# Main.net
KiCad netlist of a schematic drawn in Altium Designer
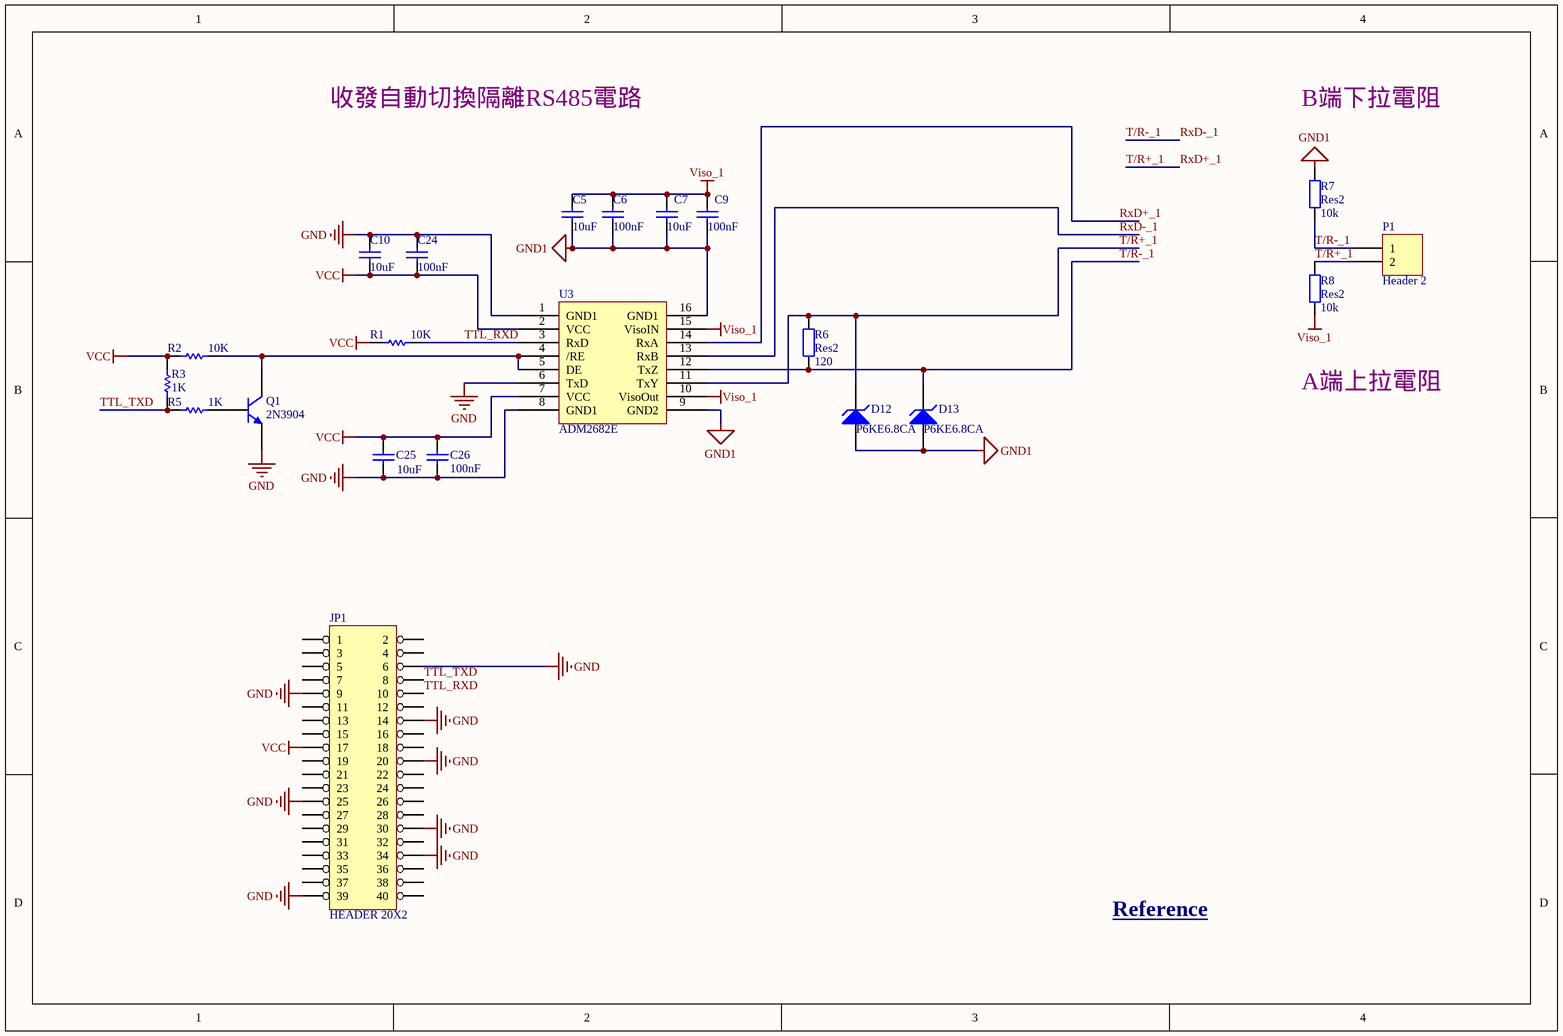
[diagram p0: Main.SchDoc]

(export (version "E")
  (design (tool "Eeschema 10.0.6"))
  (components
    (comp (ref "C5")
      (value "10uF")
      (footprint "0805_C")
      (description "Cap-10uF")
      (fields (field (name "Comment") "Cap Semi") (field (name "PUBLISHER") "Altium Limited"))
      (libsource (lib "Miscellaneous Devices") (part "Cap Semi"))
    )
    (comp (ref "C6")
      (value "100nF")
      (footprint "SMD-0402C")
      (description "Cap-0.1uF")
      (fields (field (name "Comment") "Cap Semi") (field (name "PUBLISHER") "Altium Limited"))
      (libsource (lib "Miscellaneous Devices") (part "Cap Semi"))
    )
    (comp (ref "C7")
      (value "10uF")
      (footprint "0805_C")
      (description "Cap-10uF")
      (fields (field (name "Comment") "Cap Semi") (field (name "PUBLISHER") "Altium Limited"))
      (libsource (lib "Miscellaneous Devices") (part "Cap Semi"))
    )
    (comp (ref "C9")
      (value "100nF")
      (footprint "SMD-0402C")
      (description "Cap-0.1uF")
      (fields (field (name "Comment") "Cap Semi") (field (name "PUBLISHER") "Altium Limited"))
      (libsource (lib "Miscellaneous Devices") (part "Cap Semi"))
    )
    (comp (ref "C10")
      (value "10uF")
      (footprint "0805_C")
      (description "Cap-10uF")
      (fields (field (name "Comment") "Cap Semi") (field (name "PUBLISHER") "Altium Limited"))
      (libsource (lib "Miscellaneous Devices") (part "Cap Semi"))
    )
    (comp (ref "C24")
      (value "100nF")
      (footprint "SMD-0402C")
      (description "Cap-0.1uF")
      (fields (field (name "Comment") "Cap Semi") (field (name "PUBLISHER") "Altium Limited"))
      (libsource (lib "Miscellaneous Devices") (part "Cap Semi"))
    )
    (comp (ref "C25")
      (value "10uF")
      (footprint "0805_C")
      (description "Cap-10uF")
      (fields (field (name "Comment") "Cap Semi") (field (name "PUBLISHER") "Altium Limited"))
      (libsource (lib "Miscellaneous Devices") (part "Cap Semi"))
    )
    (comp (ref "C26")
      (value "100nF")
      (footprint "SMD-0402C")
      (description "Cap-0.1uF")
      (fields (field (name "Comment") "Cap Semi") (field (name "PUBLISHER") "Altium Limited"))
      (libsource (lib "Miscellaneous Devices") (part "Cap Semi"))
    )
    (comp (ref "D12")
      (value "P6KE6.8CA")
      (footprint "DIODE-0.4")
      (description "Zener Diode")
      (fields (field (name "PUBLISHER") "Altium Limited"))
      (libsource (lib "i-SchLib") (part "D Zener"))
    )
    (comp (ref "D13")
      (value "P6KE6.8CA")
      (footprint "DIODE-0.4")
      (description "Zener Diode")
      (fields (field (name "PUBLISHER") "Altium Limited"))
      (libsource (lib "i-SchLib") (part "D Zener"))
    )
    (comp (ref "JP1")
      (value "HEADER 20X2")
      (footprint "HDR2X20")
      (libsource (lib "YB070WVHB01-50O-E1-SCH") (part "HEADER 20X2"))
    )
    (comp (ref "P1")
      (value "Header 2")
      (footprint "歐式端子*2p")
      (description "Header, 2-Pin")
      (fields (field (name "PUBLISHER") "Altium Limited"))
      (libsource (lib "Miscellaneous Connectors") (part "Header 2"))
    )
    (comp (ref "Q1")
      (value "2N3904")
      (footprint "SOT23_N")
      (description "NPN General Purpose Amplifier")
      (fields (field (name "PUBLISHER") "Altium Limited"))
      (libsource (lib "Miscellaneous Devices") (part "2N3904"))
    )
    (comp (ref "R1")
      (value "10K")
      (footprint "SMD-0402-RES")
      (description "Res-10k")
      (fields (field (name "Comment") "Res Semi") (field (name "PUBLISHER") "Altium Limited"))
      (libsource (lib "Miscellaneous Devices") (part "Res Semi"))
    )
    (comp (ref "R2")
      (value "10K")
      (footprint "SMD-0402-RES")
      (description "Res-10k")
      (fields (field (name "Comment") "Res Semi") (field (name "PUBLISHER") "Altium Limited"))
      (libsource (lib "Miscellaneous Devices") (part "Res Semi"))
    )
    (comp (ref "R3")
      (value "1K")
      (footprint "SMD-0402-RES")
      (description "Res-1k")
      (fields (field (name "Comment") "Res Semi") (field (name "PUBLISHER") "Altium Limited"))
      (libsource (lib "Miscellaneous Devices") (part "Res Semi"))
    )
    (comp (ref "R5")
      (value "1K")
      (footprint "SMD-0402-RES")
      (description "Res-1k")
      (fields (field (name "Comment") "Res Semi") (field (name "PUBLISHER") "Altium Limited"))
      (libsource (lib "Miscellaneous Devices") (part "Res Semi"))
    )
    (comp (ref "R6")
      (value "Res2")
      (footprint "SMD-0402-RES")
      (description "Res-120")
      (fields (field (name "ALTIUM_VALUE") "120") (field (name "PUBLISHER") "Altium Limited"))
      (libsource (lib "Miscellaneous Devices") (part "Res2"))
    )
    (comp (ref "R7")
      (value "Res2")
      (footprint "SMD-0402-RES")
      (description "Res-10k")
      (fields (field (name "ALTIUM_VALUE") "10k") (field (name "PUBLISHER") "Altium Limited"))
      (libsource (lib "Miscellaneous Devices") (part "Res2"))
    )
    (comp (ref "R8")
      (value "Res2")
      (footprint "SMD-0402-RES")
      (description "Res-10k")
      (fields (field (name "ALTIUM_VALUE") "10k") (field (name "PUBLISHER") "Altium Limited"))
      (libsource (lib "Miscellaneous Devices") (part "Res2"))
    )
    (comp (ref "U3")
      (value "ADM2682E")
      (footprint "SOIC127P1030-16N")
      (description "isolation RS422 with isolated power")
      (libsource (lib "i-SchLib") (part "ADM2682E"))
    )
  )
  (nets
    (net (code "1") (name "/RxD+_1") (class "Default")
      (node (ref "D12") (pin "2") (pinfunction "K_2") (pintype "passive"))
      (node (ref "P1") (pin "2") (pinfunction "2_2") (pintype "passive"))
      (node (ref "R6") (pin "2") (pinfunction "2_2") (pintype "passive"))
      (node (ref "R8") (pin "2") (pinfunction "2_2") (pintype "passive"))
      (node (ref "U3") (pin "11") (pinfunction "TxY_11") (pintype "passive"))
      (node (ref "U3") (pin "14") (pinfunction "RxA_14") (pintype "passive"))
    )
    (net (code "2") (name "/RxD-_1") (class "Default")
      (node (ref "D13") (pin "2") (pinfunction "K_2") (pintype "passive"))
      (node (ref "P1") (pin "1") (pinfunction "1_1") (pintype "passive"))
      (node (ref "R6") (pin "1") (pinfunction "1_1") (pintype "passive"))
      (node (ref "R7") (pin "1") (pinfunction "1_1") (pintype "passive"))
      (node (ref "U3") (pin "12") (pinfunction "TxZ_12") (pintype "passive"))
      (node (ref "U3") (pin "13") (pinfunction "RxB_13") (pintype "passive"))
    )
    (net (code "3") (name "/TTL_RXD") (class "Default")
      (node (ref "JP1") (pin "10") (pinfunction "10_10") (pintype "passive"))
      (node (ref "R1") (pin "1") (pinfunction "1_1") (pintype "passive"))
      (node (ref "U3") (pin "3") (pinfunction "RxD_3") (pintype "passive"))
    )
    (net (code "4") (name "/TTL_TXD") (class "Default")
      (node (ref "JP1") (pin "8") (pinfunction "8_8") (pintype "passive"))
      (node (ref "R3") (pin "2") (pinfunction "2_2") (pintype "passive"))
      (node (ref "R5") (pin "2") (pinfunction "2_2") (pintype "passive"))
    )
    (net (code "5") (name "GND") (class "Default")
      (node (ref "C10") (pin "2") (pinfunction "2_2") (pintype "passive"))
      (node (ref "C24") (pin "2") (pinfunction "2_2") (pintype "passive"))
      (node (ref "C25") (pin "1") (pinfunction "1_1") (pintype "passive"))
      (node (ref "C26") (pin "2") (pinfunction "2_2") (pintype "passive"))
      (node (ref "JP1") (pin "14") (pinfunction "14_14") (pintype "passive"))
      (node (ref "JP1") (pin "20") (pinfunction "20_20") (pintype "passive"))
      (node (ref "JP1") (pin "25") (pinfunction "25_25") (pintype "passive"))
      (node (ref "JP1") (pin "30") (pinfunction "30_30") (pintype "passive"))
      (node (ref "JP1") (pin "34") (pinfunction "34_34") (pintype "passive"))
      (node (ref "JP1") (pin "39") (pinfunction "39_39") (pintype "passive"))
      (node (ref "JP1") (pin "6") (pinfunction "6_6") (pintype "passive"))
      (node (ref "JP1") (pin "9") (pinfunction "9_9") (pintype "passive"))
      (node (ref "Q1") (pin "2") (pinfunction "E_2") (pintype "passive"))
      (node (ref "U3") (pin "1") (pinfunction "GND1_1") (pintype "passive"))
      (node (ref "U3") (pin "6") (pinfunction "TxD_6") (pintype "passive"))
      (node (ref "U3") (pin "8") (pinfunction "GND1_8") (pintype "passive"))
    )
    (net (code "6") (name "GND1") (class "Default")
      (node (ref "C5") (pin "1") (pinfunction "1_1") (pintype "passive"))
      (node (ref "C6") (pin "1") (pinfunction "1_1") (pintype "passive"))
      (node (ref "C7") (pin "1") (pinfunction "1_1") (pintype "passive"))
      (node (ref "C9") (pin "1") (pinfunction "1_1") (pintype "passive"))
      (node (ref "D12") (pin "1") (pinfunction "A_1") (pintype "passive"))
      (node (ref "D13") (pin "1") (pinfunction "A_1") (pintype "passive"))
      (node (ref "R7") (pin "2") (pinfunction "2_2") (pintype "passive"))
      (node (ref "U3") (pin "16") (pinfunction "GND1_16") (pintype "passive"))
      (node (ref "U3") (pin "9") (pinfunction "GND2_9") (pintype "passive"))
    )
    (net (code "7") (name "Net-(Q1-B)") (class "Default")
      (node (ref "Q1") (pin "3") (pinfunction "B_3") (pintype "passive"))
      (node (ref "R5") (pin "1") (pinfunction "1_1") (pintype "passive"))
    )
    (net (code "8") (name "Net-(Q1-C)") (class "Default")
      (node (ref "Q1") (pin "1") (pinfunction "C_1") (pintype "passive"))
      (node (ref "R2") (pin "1") (pinfunction "1_1") (pintype "passive"))
      (node (ref "U3") (pin "4") (pinfunction "/RE_4") (pintype "passive"))
      (node (ref "U3") (pin "5") (pinfunction "DE_5") (pintype "passive"))
    )
    (net (code "9") (name "VCC") (class "Default")
      (node (ref "C10") (pin "1") (pinfunction "1_1") (pintype "passive"))
      (node (ref "C24") (pin "1") (pinfunction "1_1") (pintype "passive"))
      (node (ref "C25") (pin "2") (pinfunction "2_2") (pintype "passive"))
      (node (ref "C26") (pin "1") (pinfunction "1_1") (pintype "passive"))
      (node (ref "JP1") (pin "17") (pinfunction "17_17") (pintype "passive"))
      (node (ref "R1") (pin "2") (pinfunction "2_2") (pintype "passive"))
      (node (ref "R2") (pin "2") (pinfunction "2_2") (pintype "passive"))
      (node (ref "R3") (pin "1") (pinfunction "1_1") (pintype "passive"))
      (node (ref "U3") (pin "2") (pinfunction "VCC_2") (pintype "passive"))
      (node (ref "U3") (pin "7") (pinfunction "VCC_7") (pintype "passive"))
    )
    (net (code "10") (name "Viso_1") (class "Default")
      (node (ref "C5") (pin "2") (pinfunction "2_2") (pintype "passive"))
      (node (ref "C6") (pin "2") (pinfunction "2_2") (pintype "passive"))
      (node (ref "C7") (pin "2") (pinfunction "2_2") (pintype "passive"))
      (node (ref "C9") (pin "2") (pinfunction "2_2") (pintype "passive"))
      (node (ref "R8") (pin "1") (pinfunction "1_1") (pintype "passive"))
      (node (ref "U3") (pin "10") (pinfunction "VisoOut_10") (pintype "passive"))
      (node (ref "U3") (pin "15") (pinfunction "VisoIN_15") (pintype "passive"))
    )
    (net (code "11") (name "unconnected-(JP1-Pad1)") (class "Default")
      (node (ref "JP1") (pin "1") (pinfunction "1_1") (pintype "passive"))
    )
    (net (code "12") (name "unconnected-(JP1-Pad2)") (class "Default")
      (node (ref "JP1") (pin "2") (pinfunction "2_2") (pintype "passive"))
    )
    (net (code "13") (name "unconnected-(JP1-Pad3)") (class "Default")
      (node (ref "JP1") (pin "3") (pinfunction "3_3") (pintype "passive"))
    )
    (net (code "14") (name "unconnected-(JP1-Pad4)") (class "Default")
      (node (ref "JP1") (pin "4") (pinfunction "4_4") (pintype "passive"))
    )
    (net (code "15") (name "unconnected-(JP1-Pad5)") (class "Default")
      (node (ref "JP1") (pin "5") (pinfunction "5_5") (pintype "passive"))
    )
    (net (code "16") (name "unconnected-(JP1-Pad7)") (class "Default")
      (node (ref "JP1") (pin "7") (pinfunction "7_7") (pintype "passive"))
    )
    (net (code "17") (name "unconnected-(JP1-Pad11)") (class "Default")
      (node (ref "JP1") (pin "11") (pinfunction "11_11") (pintype "passive"))
    )
    (net (code "18") (name "unconnected-(JP1-Pad12)") (class "Default")
      (node (ref "JP1") (pin "12") (pinfunction "12_12") (pintype "passive"))
    )
    (net (code "19") (name "unconnected-(JP1-Pad13)") (class "Default")
      (node (ref "JP1") (pin "13") (pinfunction "13_13") (pintype "passive"))
    )
    (net (code "20") (name "unconnected-(JP1-Pad15)") (class "Default")
      (node (ref "JP1") (pin "15") (pinfunction "15_15") (pintype "passive"))
    )
    (net (code "21") (name "unconnected-(JP1-Pad16)") (class "Default")
      (node (ref "JP1") (pin "16") (pinfunction "16_16") (pintype "passive"))
    )
    (net (code "22") (name "unconnected-(JP1-Pad18)") (class "Default")
      (node (ref "JP1") (pin "18") (pinfunction "18_18") (pintype "passive"))
    )
    (net (code "23") (name "unconnected-(JP1-Pad19)") (class "Default")
      (node (ref "JP1") (pin "19") (pinfunction "19_19") (pintype "passive"))
    )
    (net (code "24") (name "unconnected-(JP1-Pad21)") (class "Default")
      (node (ref "JP1") (pin "21") (pinfunction "21_21") (pintype "passive"))
    )
    (net (code "25") (name "unconnected-(JP1-Pad22)") (class "Default")
      (node (ref "JP1") (pin "22") (pinfunction "22_22") (pintype "passive"))
    )
    (net (code "26") (name "unconnected-(JP1-Pad23)") (class "Default")
      (node (ref "JP1") (pin "23") (pinfunction "23_23") (pintype "passive"))
    )
    (net (code "27") (name "unconnected-(JP1-Pad24)") (class "Default")
      (node (ref "JP1") (pin "24") (pinfunction "24_24") (pintype "passive"))
    )
    (net (code "28") (name "unconnected-(JP1-Pad26)") (class "Default")
      (node (ref "JP1") (pin "26") (pinfunction "26_26") (pintype "passive"))
    )
    (net (code "29") (name "unconnected-(JP1-Pad27)") (class "Default")
      (node (ref "JP1") (pin "27") (pinfunction "27_27") (pintype "passive"))
    )
    (net (code "30") (name "unconnected-(JP1-Pad28)") (class "Default")
      (node (ref "JP1") (pin "28") (pinfunction "28_28") (pintype "passive"))
    )
    (net (code "31") (name "unconnected-(JP1-Pad29)") (class "Default")
      (node (ref "JP1") (pin "29") (pinfunction "29_29") (pintype "passive"))
    )
    (net (code "32") (name "unconnected-(JP1-Pad31)") (class "Default")
      (node (ref "JP1") (pin "31") (pinfunction "31_31") (pintype "passive"))
    )
    (net (code "33") (name "unconnected-(JP1-Pad32)") (class "Default")
      (node (ref "JP1") (pin "32") (pinfunction "32_32") (pintype "passive"))
    )
    (net (code "34") (name "unconnected-(JP1-Pad33)") (class "Default")
      (node (ref "JP1") (pin "33") (pinfunction "33_33") (pintype "passive"))
    )
    (net (code "35") (name "unconnected-(JP1-Pad35)") (class "Default")
      (node (ref "JP1") (pin "35") (pinfunction "35_35") (pintype "passive"))
    )
    (net (code "36") (name "unconnected-(JP1-Pad36)") (class "Default")
      (node (ref "JP1") (pin "36") (pinfunction "36_36") (pintype "passive"))
    )
    (net (code "37") (name "unconnected-(JP1-Pad37)") (class "Default")
      (node (ref "JP1") (pin "37") (pinfunction "37_37") (pintype "passive"))
    )
    (net (code "38") (name "unconnected-(JP1-Pad38)") (class "Default")
      (node (ref "JP1") (pin "38") (pinfunction "38_38") (pintype "passive"))
    )
    (net (code "39") (name "unconnected-(JP1-Pad40)") (class "Default")
      (node (ref "JP1") (pin "40") (pinfunction "40_40") (pintype "passive"))
    )
  )
)
